# save.net
KiCad netlist of a schematic drawn in EAGLE
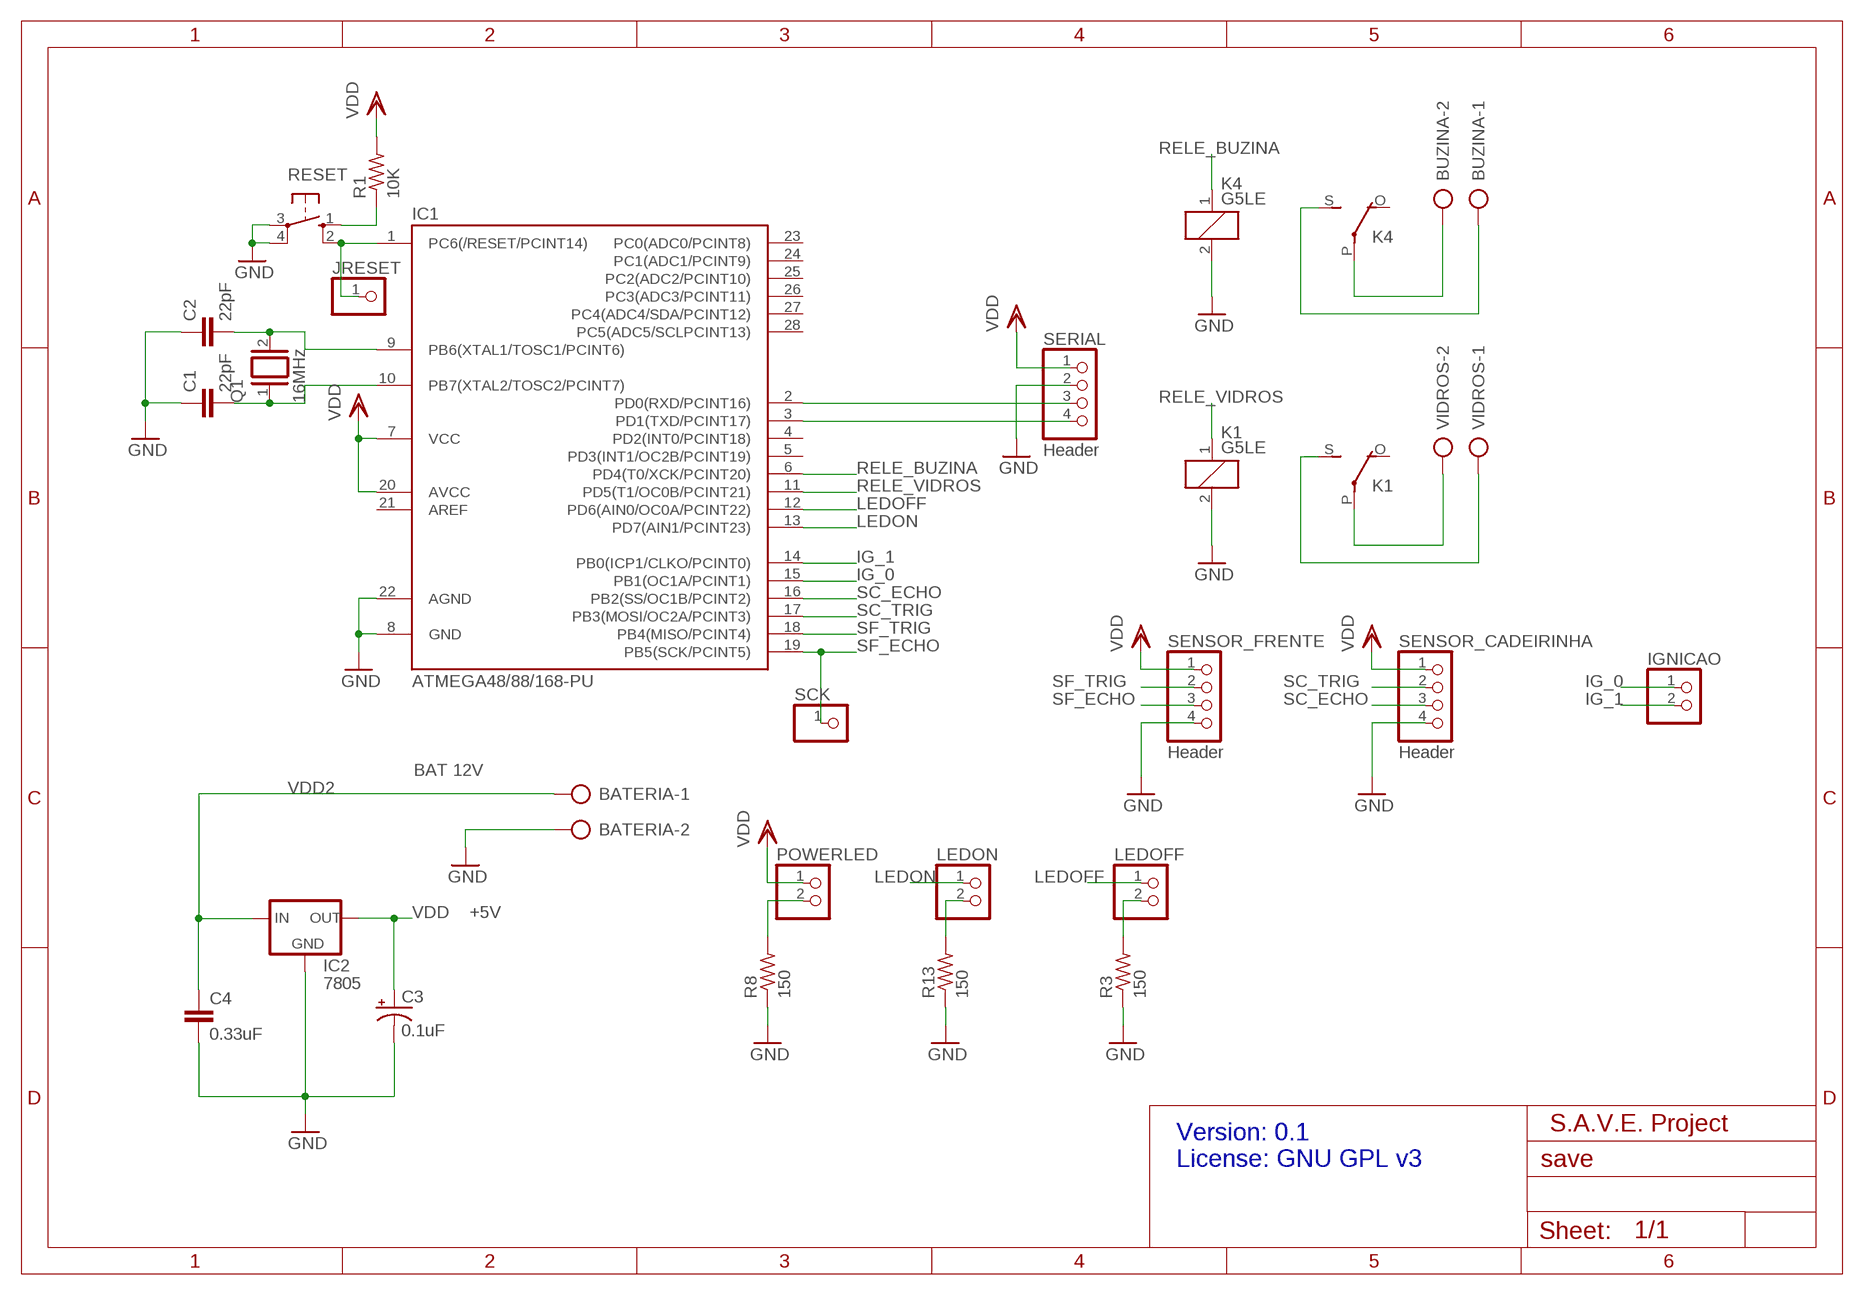
[diagram p0: schematic, sheet 1]

(export (version "E")
  (design (tool "Eeschema 10.0.6"))
  (components
    (comp (ref "BATERIA")
      (value "AK300/2")
      (footprint "eagle-import:AK300_2")
      (libsource (lib "eagle-import") (part "AK300/2"))
    )
    (comp (ref "BUZINA")
      (value "AK300/2")
      (footprint "eagle-import:AK300_2")
      (libsource (lib "eagle-import") (part "AK300/2"))
    )
    (comp (ref "C1")
      (value "22pF")
      (footprint "eagle-import:C050-024X044")
      (libsource (lib "eagle-import") (part "C-EU050-024X044"))
    )
    (comp (ref "C2")
      (value "22pF")
      (footprint "eagle-import:C050-024X044")
      (libsource (lib "eagle-import") (part "C-EU050-024X044"))
    )
    (comp (ref "C3")
      (value "0.1uF")
      (footprint "eagle-import:E2-4")
      (libsource (lib "eagle-import") (part "CPOL-USE2-4"))
    )
    (comp (ref "C4")
      (value "0.33uF")
      (footprint "eagle-import:C025-030X050")
      (libsource (lib "eagle-import") (part "resistor_C-EU025-030X050"))
    )
    (comp (ref "IC1")
      (value "ATMEGA48/88/168-PU")
      (footprint "eagle-import:DIL28-3")
      (libsource (lib "eagle-import") (part "ATMEGA48/88/168-PU"))
    )
    (comp (ref "IC2")
      (value "7805")
      (footprint "eagle-import:78XXL")
      (libsource (lib "eagle-import") (part "78XXL"))
    )
    (comp (ref "IGNICAO")
      (value "PINHD-1X2/90")
      (footprint "eagle-import:1X02_90")
      (libsource (lib "eagle-import") (part "PINHD-1X2/90"))
    )
    (comp (ref "JRESET")
      (value "PINHD-1X1")
      (footprint "eagle-import:1X01")
      (libsource (lib "eagle-import") (part "PINHD-1X1"))
    )
    (comp (ref "K1")
      (value "G5LE")
      (footprint "eagle-import:G5LE")
      (libsource (lib "eagle-import") (part "G5LE"))
    )
    (comp (ref "K4")
      (value "G5LE")
      (footprint "eagle-import:G5LE")
      (libsource (lib "eagle-import") (part "G5LE"))
    )
    (comp (ref "LEDOFF")
      (value "PINHD-1X2/90")
      (footprint "eagle-import:1X02_90")
      (libsource (lib "eagle-import") (part "PINHD-1X2/90"))
    )
    (comp (ref "LEDON")
      (value "PINHD-1X2/90")
      (footprint "eagle-import:1X02_90")
      (libsource (lib "eagle-import") (part "PINHD-1X2/90"))
    )
    (comp (ref "POWERLED")
      (value "PINHD-1X2/90")
      (footprint "eagle-import:1X02_90")
      (libsource (lib "eagle-import") (part "PINHD-1X2/90"))
    )
    (comp (ref "Q1")
      (value "16MHz")
      (footprint "eagle-import:QS")
      (libsource (lib "eagle-import") (part "XTAL/S"))
    )
    (comp (ref "R1")
      (value "10K")
      (footprint "eagle-import:0207_10")
      (libsource (lib "eagle-import") (part "R-US_0207/10"))
    )
    (comp (ref "R3")
      (value "150")
      (footprint "eagle-import:0207_10")
      (libsource (lib "eagle-import") (part "R-US_0207/10"))
    )
    (comp (ref "R8")
      (value "150")
      (footprint "eagle-import:0207_10")
      (libsource (lib "eagle-import") (part "R-US_0207/10"))
    )
    (comp (ref "R13")
      (value "150")
      (footprint "eagle-import:0207_10")
      (libsource (lib "eagle-import") (part "R-US_0207/10"))
    )
    (comp (ref "RESET")
      (value "10-XX")
      (footprint "eagle-import:B3F-10XX")
      (fields (field (name "MPN") "B3F-1000"))
      (libsource (lib "eagle-import") (part "10-XX"))
    )
    (comp (ref "SCK")
      (value "PINHD-1X1")
      (footprint "eagle-import:1X01")
      (libsource (lib "eagle-import") (part "PINHD-1X1"))
    )
    (comp (ref "SENSOR_CADEIRINHA")
      (value "Header")
      (footprint "eagle-import:1X04")
      (libsource (lib "eagle-import") (part "PINHD-1X4"))
    )
    (comp (ref "SENSOR_FRENTE")
      (value "Header")
      (footprint "eagle-import:1X04")
      (libsource (lib "eagle-import") (part "PINHD-1X4"))
    )
    (comp (ref "SERIAL")
      (value "Header")
      (footprint "eagle-import:1X04")
      (libsource (lib "eagle-import") (part "PINHD-1X4"))
    )
    (comp (ref "VIDROS")
      (value "AK300/2")
      (footprint "eagle-import:AK300_2")
      (libsource (lib "eagle-import") (part "AK300/2"))
    )
  )
  (nets
    (net (code "1") (name "/IG_0") (class "Default")
      (node (ref "IC1") (pin "15") (pinfunction "PB1(OC1A/PCINT1)_15") (pintype "bidirectional"))
      (node (ref "IGNICAO") (pin "1") (pinfunction "1_1") (pintype "passive"))
    )
    (net (code "2") (name "/IG_1") (class "Default")
      (node (ref "IC1") (pin "14") (pinfunction "PB0(ICP1/CLKO/PCINT0)_14") (pintype "bidirectional"))
      (node (ref "IGNICAO") (pin "2") (pinfunction "2_2") (pintype "passive"))
    )
    (net (code "3") (name "/LEDOFF") (class "Default")
      (node (ref "IC1") (pin "12") (pinfunction "PD6(AIN0/OC0A/PCINT22)_12") (pintype "bidirectional"))
      (node (ref "LEDOFF") (pin "1") (pinfunction "1_1") (pintype "passive"))
    )
    (net (code "4") (name "/LEDON") (class "Default")
      (node (ref "IC1") (pin "13") (pinfunction "PD7(AIN1/PCINT23)_13") (pintype "bidirectional"))
      (node (ref "LEDON") (pin "1") (pinfunction "1_1") (pintype "passive"))
    )
    (net (code "5") (name "/RELE_BUZINA") (class "Default")
      (node (ref "IC1") (pin "6") (pinfunction "PD4(T0/XCK/PCINT20)_6") (pintype "bidirectional"))
      (node (ref "K4") (pin "1") (pinfunction "1_1") (pintype "passive"))
    )
    (net (code "6") (name "/RELE_VIDROS") (class "Default")
      (node (ref "IC1") (pin "11") (pinfunction "PD5(T1/OC0B/PCINT21)_11") (pintype "bidirectional"))
      (node (ref "K1") (pin "1") (pinfunction "1_1") (pintype "passive"))
    )
    (net (code "7") (name "/SC_ECHO") (class "Default")
      (node (ref "IC1") (pin "16") (pinfunction "PB2(SS/OC1B/PCINT2)_16") (pintype "bidirectional"))
      (node (ref "SENSOR_CADEIRINHA") (pin "3") (pinfunction "3_3") (pintype "passive"))
    )
    (net (code "8") (name "/SC_TRIG") (class "Default")
      (node (ref "IC1") (pin "17") (pinfunction "PB3(MOSI/OC2A/PCINT3)_17") (pintype "bidirectional"))
      (node (ref "SENSOR_CADEIRINHA") (pin "2") (pinfunction "2_2") (pintype "passive"))
    )
    (net (code "9") (name "/SF_ECHO") (class "Default")
      (node (ref "IC1") (pin "19") (pinfunction "PB5(SCK/PCINT5)_19") (pintype "bidirectional"))
      (node (ref "SCK") (pin "1") (pinfunction "1_1") (pintype "passive"))
      (node (ref "SENSOR_FRENTE") (pin "3") (pinfunction "3_3") (pintype "passive"))
    )
    (net (code "10") (name "/SF_TRIG") (class "Default")
      (node (ref "IC1") (pin "18") (pinfunction "PB4(MISO/PCINT4)_18") (pintype "bidirectional"))
      (node (ref "SENSOR_FRENTE") (pin "2") (pinfunction "2_2") (pintype "passive"))
    )
    (net (code "11") (name "/VDD2") (class "Default")
      (node (ref "BATERIA") (pin "1") (pinfunction "KL_1") (pintype "passive"))
      (node (ref "C4") (pin "1") (pinfunction "1_1") (pintype "passive"))
      (node (ref "IC2") (pin "IN") (pinfunction "IN_IN") (pintype "input"))
    )
    (net (code "12") (name "GND") (class "Default")
      (node (ref "BATERIA") (pin "2") (pinfunction "KL_2") (pintype "passive"))
      (node (ref "C1") (pin "1") (pinfunction "1_1") (pintype "passive"))
      (node (ref "C2") (pin "1") (pinfunction "1_1") (pintype "passive"))
      (node (ref "C3") (pin "-") (pinfunction "-_-") (pintype "passive"))
      (node (ref "C4") (pin "2") (pinfunction "2_2") (pintype "passive"))
      (node (ref "IC1") (pin "22") (pinfunction "AGND_22") (pintype "power_in"))
      (node (ref "IC1") (pin "8") (pinfunction "GND_8") (pintype "power_in"))
      (node (ref "IC2") (pin "GND") (pinfunction "GND_GND") (pintype "input"))
      (node (ref "K1") (pin "2") (pinfunction "2_2") (pintype "passive"))
      (node (ref "K4") (pin "2") (pinfunction "2_2") (pintype "passive"))
      (node (ref "R13") (pin "1") (pinfunction "1_1") (pintype "passive"))
      (node (ref "R3") (pin "1") (pinfunction "1_1") (pintype "passive"))
      (node (ref "R8") (pin "1") (pinfunction "1_1") (pintype "passive"))
      (node (ref "RESET") (pin "3") (pinfunction "P_3") (pintype "passive"))
      (node (ref "RESET") (pin "4") (pinfunction "P1_4") (pintype "passive"))
      (node (ref "SENSOR_CADEIRINHA") (pin "4") (pinfunction "4_4") (pintype "passive"))
      (node (ref "SENSOR_FRENTE") (pin "4") (pinfunction "4_4") (pintype "passive"))
      (node (ref "SERIAL") (pin "2") (pinfunction "2_2") (pintype "passive"))
    )
    (net (code "13") (name "Net-(BUZINAA-KL)") (class "Default")
      (node (ref "BUZINA") (pin "1") (pinfunction "KL_1") (pintype "passive"))
      (node (ref "K4") (pin "S") (pinfunction "S_S") (pintype "passive"))
    )
    (net (code "14") (name "Net-(BUZINAB-KL)") (class "Default")
      (node (ref "BUZINA") (pin "2") (pinfunction "KL_2") (pintype "passive"))
      (node (ref "K4") (pin "P") (pinfunction "P_P") (pintype "passive"))
    )
    (net (code "15") (name "Net-(IC1-PB6(XTAL1{slash}TOSC1{slash}PCINT6))") (class "Default")
      (node (ref "C2") (pin "2") (pinfunction "2_2") (pintype "passive"))
      (node (ref "IC1") (pin "9") (pinfunction "PB6(XTAL1/TOSC1/PCINT6)_9") (pintype "bidirectional"))
      (node (ref "Q1") (pin "2") (pinfunction "2_2") (pintype "passive"))
    )
    (net (code "16") (name "Net-(IC1-PB7(XTAL2{slash}TOSC2{slash}PCINT7))") (class "Default")
      (node (ref "C1") (pin "2") (pinfunction "2_2") (pintype "passive"))
      (node (ref "IC1") (pin "10") (pinfunction "PB7(XTAL2/TOSC2/PCINT7)_10") (pintype "bidirectional"))
      (node (ref "Q1") (pin "1") (pinfunction "1_1") (pintype "passive"))
    )
    (net (code "17") (name "Net-(IC1-PC6({slash}RESET{slash}PCINT14))") (class "Default")
      (node (ref "IC1") (pin "1") (pinfunction "PC6(/RESET/PCINT14)_1") (pintype "bidirectional"))
      (node (ref "JRESET") (pin "1") (pinfunction "1_1") (pintype "passive"))
      (node (ref "RESET") (pin "2") (pinfunction "S1_2") (pintype "passive"))
    )
    (net (code "18") (name "Net-(IC1-PD0(RXD{slash}PCINT16))") (class "Default")
      (node (ref "IC1") (pin "2") (pinfunction "PD0(RXD/PCINT16)_2") (pintype "bidirectional"))
      (node (ref "SERIAL") (pin "3") (pinfunction "3_3") (pintype "passive"))
    )
    (net (code "19") (name "Net-(IC1-PD1(TXD{slash}PCINT17))") (class "Default")
      (node (ref "IC1") (pin "3") (pinfunction "PD1(TXD/PCINT17)_3") (pintype "bidirectional"))
      (node (ref "SERIAL") (pin "4") (pinfunction "4_4") (pintype "passive"))
    )
    (net (code "20") (name "Net-(LEDOFF-Pad2)") (class "Default")
      (node (ref "LEDOFF") (pin "2") (pinfunction "2_2") (pintype "passive"))
      (node (ref "R3") (pin "2") (pinfunction "2_2") (pintype "passive"))
    )
    (net (code "21") (name "Net-(LEDON-Pad2)") (class "Default")
      (node (ref "LEDON") (pin "2") (pinfunction "2_2") (pintype "passive"))
      (node (ref "R13") (pin "2") (pinfunction "2_2") (pintype "passive"))
    )
    (net (code "22") (name "Net-(POWERLED-Pad2)") (class "Default")
      (node (ref "POWERLED") (pin "2") (pinfunction "2_2") (pintype "passive"))
      (node (ref "R8") (pin "2") (pinfunction "2_2") (pintype "passive"))
    )
    (net (code "23") (name "Net-(RESET-S)") (class "Default")
      (node (ref "R1") (pin "1") (pinfunction "1_1") (pintype "passive"))
      (node (ref "RESET") (pin "1") (pinfunction "S_1") (pintype "passive"))
    )
    (net (code "24") (name "Net-(VIDROSA-KL)") (class "Default")
      (node (ref "K1") (pin "S") (pinfunction "S_S") (pintype "passive"))
      (node (ref "VIDROS") (pin "1") (pinfunction "KL_1") (pintype "passive"))
    )
    (net (code "25") (name "Net-(VIDROSB-KL)") (class "Default")
      (node (ref "K1") (pin "P") (pinfunction "P_P") (pintype "passive"))
      (node (ref "VIDROS") (pin "2") (pinfunction "KL_2") (pintype "passive"))
    )
    (net (code "26") (name "VDD") (class "Default")
      (node (ref "C3") (pin "+") (pinfunction "+_+") (pintype "passive"))
      (node (ref "IC1") (pin "20") (pinfunction "AVCC_20") (pintype "passive"))
      (node (ref "IC1") (pin "7") (pinfunction "VCC_7") (pintype "power_in"))
      (node (ref "IC2") (pin "OUT") (pinfunction "OUT_OUT") (pintype "passive"))
      (node (ref "POWERLED") (pin "1") (pinfunction "1_1") (pintype "passive"))
      (node (ref "R1") (pin "2") (pinfunction "2_2") (pintype "passive"))
      (node (ref "SENSOR_CADEIRINHA") (pin "1") (pinfunction "1_1") (pintype "passive"))
      (node (ref "SENSOR_FRENTE") (pin "1") (pinfunction "1_1") (pintype "passive"))
      (node (ref "SERIAL") (pin "1") (pinfunction "1_1") (pintype "passive"))
    )
    (net (code "27") (name "unconnected-(IC1-AREF-Pad21)") (class "Default")
      (node (ref "IC1") (pin "21") (pinfunction "AREF_21") (pintype "passive"))
    )
    (net (code "28") (name "unconnected-(IC1-PC0(ADC0{slash}PCINT8)-Pad23)") (class "Default")
      (node (ref "IC1") (pin "23") (pinfunction "PC0(ADC0/PCINT8)_23") (pintype "bidirectional"))
    )
    (net (code "29") (name "unconnected-(IC1-PC1(ADC1{slash}PCINT9)-Pad24)") (class "Default")
      (node (ref "IC1") (pin "24") (pinfunction "PC1(ADC1/PCINT9)_24") (pintype "bidirectional"))
    )
    (net (code "30") (name "unconnected-(IC1-PC2(ADC2{slash}PCINT10)-Pad25)") (class "Default")
      (node (ref "IC1") (pin "25") (pinfunction "PC2(ADC2/PCINT10)_25") (pintype "bidirectional"))
    )
    (net (code "31") (name "unconnected-(IC1-PC3(ADC3{slash}PCINT11)-Pad26)") (class "Default")
      (node (ref "IC1") (pin "26") (pinfunction "PC3(ADC3/PCINT11)_26") (pintype "bidirectional"))
    )
    (net (code "32") (name "unconnected-(IC1-PC4(ADC4{slash}SDA{slash}PCINT12)-Pad27)") (class "Default")
      (node (ref "IC1") (pin "27") (pinfunction "PC4(ADC4/SDA/PCINT12)_27") (pintype "bidirectional"))
    )
    (net (code "33") (name "unconnected-(IC1-PC5(ADC5{slash}SCLPCINT13)-Pad28)") (class "Default")
      (node (ref "IC1") (pin "28") (pinfunction "PC5(ADC5/SCLPCINT13)_28") (pintype "bidirectional"))
    )
    (net (code "34") (name "unconnected-(IC1-PD2(INT0{slash}PCINT18)-Pad4)") (class "Default")
      (node (ref "IC1") (pin "4") (pinfunction "PD2(INT0/PCINT18)_4") (pintype "bidirectional"))
    )
    (net (code "35") (name "unconnected-(IC1-PD3(INT1{slash}OC2B{slash}PCINT19)-Pad5)") (class "Default")
      (node (ref "IC1") (pin "5") (pinfunction "PD3(INT1/OC2B/PCINT19)_5") (pintype "bidirectional"))
    )
    (net (code "36") (name "unconnected-(K1-PadO)") (class "Default")
      (node (ref "K1") (pin "O") (pinfunction "O_O") (pintype "passive"))
    )
    (net (code "37") (name "unconnected-(K4-PadO)") (class "Default")
      (node (ref "K4") (pin "O") (pinfunction "O_O") (pintype "passive"))
    )
  )
)
